# 74LVC2G157_breakout.net
KiCad netlist of a schematic drawn in EAGLE
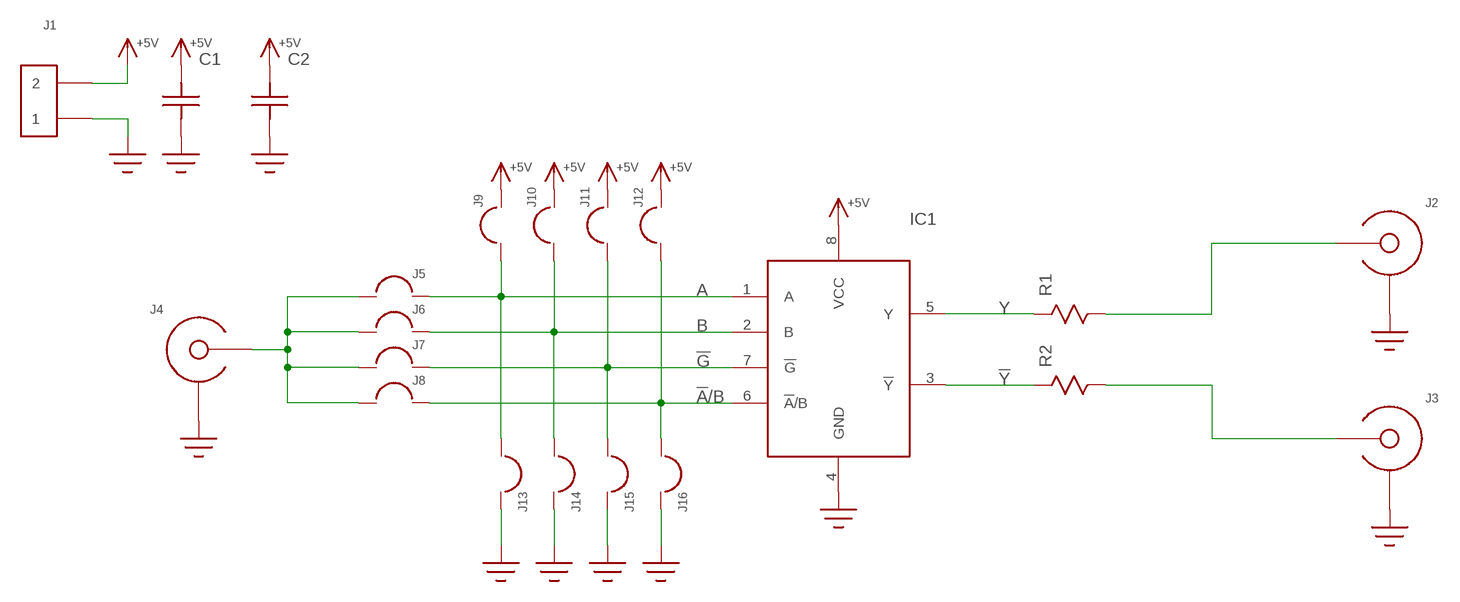
[diagram p0: schematic, sheet 1]

(export (version "E")
  (design (tool "Eeschema 10.0.6"))
  (components
    (comp (ref "C1")
      (value "C0603")
      (footprint "eagle-import:C0603")
      (libsource (lib "eagle-import") (part "C0603"))
    )
    (comp (ref "C2")
      (value "C1206")
      (footprint "eagle-import:1206")
      (libsource (lib "eagle-import") (part "C1206"))
    )
    (comp (ref "IC1")
      (value "74LVC2G157")
      (footprint "eagle-import:SSOP8")
      (libsource (lib "eagle-import") (part "74LVC2G157"))
    )
    (comp (ref "J1")
      (value "HEADER_2PIN")
      (footprint "eagle-import:HEADER_2PIN")
      (libsource (lib "eagle-import") (part "HEADER_2PIN"))
    )
    (comp (ref "J2")
      (value "EDGE_LAUNCH_JACKNARROW")
      (footprint "eagle-import:EDGE_LAUNCH_RF_CON_NARROW")
      (libsource (lib "eagle-import") (part "EDGE_LAUNCH_JACKNARROW"))
    )
    (comp (ref "J3")
      (value "EDGE_LAUNCH_JACKNARROW")
      (footprint "eagle-import:EDGE_LAUNCH_RF_CON_NARROW")
      (libsource (lib "eagle-import") (part "EDGE_LAUNCH_JACKNARROW"))
    )
    (comp (ref "J4")
      (value "EDGE_LAUNCH_JACKNARROW")
      (footprint "eagle-import:EDGE_LAUNCH_RF_CON_NARROW")
      (libsource (lib "eagle-import") (part "EDGE_LAUNCH_JACKNARROW"))
    )
    (comp (ref "J5")
      (value "SOLDER_BRIDGE")
      (footprint "eagle-import:SOLDER_BRIDGE")
      (libsource (lib "eagle-import") (part "SOLDER_BRIDGE"))
    )
    (comp (ref "J6")
      (value "SOLDER_BRIDGE")
      (footprint "eagle-import:SOLDER_BRIDGE")
      (libsource (lib "eagle-import") (part "SOLDER_BRIDGE"))
    )
    (comp (ref "J7")
      (value "SOLDER_BRIDGE")
      (footprint "eagle-import:SOLDER_BRIDGE")
      (libsource (lib "eagle-import") (part "SOLDER_BRIDGE"))
    )
    (comp (ref "J8")
      (value "SOLDER_BRIDGE")
      (footprint "eagle-import:SOLDER_BRIDGE")
      (libsource (lib "eagle-import") (part "SOLDER_BRIDGE"))
    )
    (comp (ref "J9")
      (value "SOLDER_BRIDGE")
      (footprint "eagle-import:SOLDER_BRIDGE")
      (libsource (lib "eagle-import") (part "SOLDER_BRIDGE"))
    )
    (comp (ref "J10")
      (value "SOLDER_BRIDGE")
      (footprint "eagle-import:SOLDER_BRIDGE")
      (libsource (lib "eagle-import") (part "SOLDER_BRIDGE"))
    )
    (comp (ref "J11")
      (value "SOLDER_BRIDGE")
      (footprint "eagle-import:SOLDER_BRIDGE")
      (libsource (lib "eagle-import") (part "SOLDER_BRIDGE"))
    )
    (comp (ref "J12")
      (value "SOLDER_BRIDGE")
      (footprint "eagle-import:SOLDER_BRIDGE")
      (libsource (lib "eagle-import") (part "SOLDER_BRIDGE"))
    )
    (comp (ref "J13")
      (value "SOLDER_BRIDGE")
      (footprint "eagle-import:SOLDER_BRIDGE")
      (libsource (lib "eagle-import") (part "SOLDER_BRIDGE"))
    )
    (comp (ref "J14")
      (value "SOLDER_BRIDGE")
      (footprint "eagle-import:SOLDER_BRIDGE")
      (libsource (lib "eagle-import") (part "SOLDER_BRIDGE"))
    )
    (comp (ref "J15")
      (value "SOLDER_BRIDGE")
      (footprint "eagle-import:SOLDER_BRIDGE")
      (libsource (lib "eagle-import") (part "SOLDER_BRIDGE"))
    )
    (comp (ref "J16")
      (value "SOLDER_BRIDGE")
      (footprint "eagle-import:SOLDER_BRIDGE")
      (libsource (lib "eagle-import") (part "SOLDER_BRIDGE"))
    )
    (comp (ref "R1")
      (value "R0603")
      (footprint "eagle-import:R0603")
      (libsource (lib "eagle-import") (part "R0603"))
    )
    (comp (ref "R2")
      (value "R0603")
      (footprint "eagle-import:R0603")
      (libsource (lib "eagle-import") (part "R0603"))
    )
  )
  (nets
    (net (code "1") (name "+5V") (class "Default")
      (node (ref "C1") (pin "P$2") (pinfunction "P$2_P$2") (pintype "bidirectional"))
      (node (ref "C2") (pin "P$2") (pinfunction "P$2_P$2") (pintype "bidirectional"))
      (node (ref "IC1") (pin "8") (pinfunction "VCC_8") (pintype "bidirectional"))
      (node (ref "J1") (pin "2") (pinfunction "2_2") (pintype "bidirectional"))
      (node (ref "J10") (pin "2@1") (pinfunction "P$2_2@1") (pintype "bidirectional"))
      (node (ref "J10") (pin "2@2") (pinfunction "P$2_2@2") (pintype "bidirectional"))
      (node (ref "J10") (pin "2@3") (pinfunction "P$2_2@3") (pintype "bidirectional"))
      (node (ref "J11") (pin "2@1") (pinfunction "P$2_2@1") (pintype "bidirectional"))
      (node (ref "J11") (pin "2@2") (pinfunction "P$2_2@2") (pintype "bidirectional"))
      (node (ref "J11") (pin "2@3") (pinfunction "P$2_2@3") (pintype "bidirectional"))
      (node (ref "J12") (pin "2@1") (pinfunction "P$2_2@1") (pintype "bidirectional"))
      (node (ref "J12") (pin "2@2") (pinfunction "P$2_2@2") (pintype "bidirectional"))
      (node (ref "J12") (pin "2@3") (pinfunction "P$2_2@3") (pintype "bidirectional"))
      (node (ref "J9") (pin "2@1") (pinfunction "P$2_2@1") (pintype "bidirectional"))
      (node (ref "J9") (pin "2@2") (pinfunction "P$2_2@2") (pintype "bidirectional"))
      (node (ref "J9") (pin "2@3") (pinfunction "P$2_2@3") (pintype "bidirectional"))
    )
    (net (code "2") (name "/A") (class "Default")
      (node (ref "IC1") (pin "1") (pinfunction "A_1") (pintype "bidirectional"))
      (node (ref "J13") (pin "1") (pinfunction "P$1_1") (pintype "bidirectional"))
      (node (ref "J5") (pin "2@1") (pinfunction "P$2_2@1") (pintype "bidirectional"))
      (node (ref "J5") (pin "2@2") (pinfunction "P$2_2@2") (pintype "bidirectional"))
      (node (ref "J5") (pin "2@3") (pinfunction "P$2_2@3") (pintype "bidirectional"))
      (node (ref "J9") (pin "1") (pinfunction "P$1_1") (pintype "bidirectional"))
    )
    (net (code "3") (name "/B") (class "Default")
      (node (ref "IC1") (pin "2") (pinfunction "B_2") (pintype "bidirectional"))
      (node (ref "J10") (pin "1") (pinfunction "P$1_1") (pintype "bidirectional"))
      (node (ref "J14") (pin "1") (pinfunction "P$1_1") (pintype "bidirectional"))
      (node (ref "J6") (pin "2@1") (pinfunction "P$2_2@1") (pintype "bidirectional"))
      (node (ref "J6") (pin "2@2") (pinfunction "P$2_2@2") (pintype "bidirectional"))
      (node (ref "J6") (pin "2@3") (pinfunction "P$2_2@3") (pintype "bidirectional"))
    )
    (net (code "4") (name "/Y") (class "Default")
      (node (ref "IC1") (pin "5") (pinfunction "Y_5") (pintype "bidirectional"))
      (node (ref "R1") (pin "P$1") (pinfunction "P$3_P$1") (pintype "bidirectional"))
    )
    (net (code "5") (name "/~{A}{slash}B") (class "Default")
      (node (ref "IC1") (pin "6") (pinfunction "~{A}/B_6") (pintype "bidirectional"))
      (node (ref "J12") (pin "1") (pinfunction "P$1_1") (pintype "bidirectional"))
      (node (ref "J16") (pin "1") (pinfunction "P$1_1") (pintype "bidirectional"))
      (node (ref "J8") (pin "2@1") (pinfunction "P$2_2@1") (pintype "bidirectional"))
      (node (ref "J8") (pin "2@2") (pinfunction "P$2_2@2") (pintype "bidirectional"))
      (node (ref "J8") (pin "2@3") (pinfunction "P$2_2@3") (pintype "bidirectional"))
    )
    (net (code "6") (name "/~{G}") (class "Default")
      (node (ref "IC1") (pin "7") (pinfunction "~{G}_7") (pintype "bidirectional"))
      (node (ref "J11") (pin "1") (pinfunction "P$1_1") (pintype "bidirectional"))
      (node (ref "J15") (pin "1") (pinfunction "P$1_1") (pintype "bidirectional"))
      (node (ref "J7") (pin "2@1") (pinfunction "P$2_2@1") (pintype "bidirectional"))
      (node (ref "J7") (pin "2@2") (pinfunction "P$2_2@2") (pintype "bidirectional"))
      (node (ref "J7") (pin "2@3") (pinfunction "P$2_2@3") (pintype "bidirectional"))
    )
    (net (code "7") (name "/~{Y}") (class "Default")
      (node (ref "IC1") (pin "3") (pinfunction "~{Y}_3") (pintype "bidirectional"))
      (node (ref "R2") (pin "P$1") (pinfunction "P$3_P$1") (pintype "bidirectional"))
    )
    (net (code "8") (name "GND") (class "Default")
      (node (ref "C1") (pin "P$1") (pinfunction "P$1_P$1") (pintype "bidirectional"))
      (node (ref "C2") (pin "P$1") (pinfunction "P$1_P$1") (pintype "bidirectional"))
      (node (ref "IC1") (pin "4") (pinfunction "GND_4") (pintype "bidirectional"))
      (node (ref "J1") (pin "1") (pinfunction "1_1") (pintype "bidirectional"))
      (node (ref "J13") (pin "2@1") (pinfunction "P$2_2@1") (pintype "bidirectional"))
      (node (ref "J13") (pin "2@2") (pinfunction "P$2_2@2") (pintype "bidirectional"))
      (node (ref "J13") (pin "2@3") (pinfunction "P$2_2@3") (pintype "bidirectional"))
      (node (ref "J14") (pin "2@1") (pinfunction "P$2_2@1") (pintype "bidirectional"))
      (node (ref "J14") (pin "2@2") (pinfunction "P$2_2@2") (pintype "bidirectional"))
      (node (ref "J14") (pin "2@3") (pinfunction "P$2_2@3") (pintype "bidirectional"))
      (node (ref "J15") (pin "2@1") (pinfunction "P$2_2@1") (pintype "bidirectional"))
      (node (ref "J15") (pin "2@2") (pinfunction "P$2_2@2") (pintype "bidirectional"))
      (node (ref "J15") (pin "2@3") (pinfunction "P$2_2@3") (pintype "bidirectional"))
      (node (ref "J16") (pin "2@1") (pinfunction "P$2_2@1") (pintype "bidirectional"))
      (node (ref "J16") (pin "2@2") (pinfunction "P$2_2@2") (pintype "bidirectional"))
      (node (ref "J16") (pin "2@3") (pinfunction "P$2_2@3") (pintype "bidirectional"))
      (node (ref "J2") (pin "GND@1") (pinfunction "SHIELD_GND@1") (pintype "bidirectional"))
      (node (ref "J2") (pin "GND@2") (pinfunction "SHIELD_GND@2") (pintype "bidirectional"))
      (node (ref "J2") (pin "GND@3") (pinfunction "SHIELD_GND@3") (pintype "bidirectional"))
      (node (ref "J2") (pin "GND@4") (pinfunction "SHIELD_GND@4") (pintype "bidirectional"))
      (node (ref "J2") (pin "GND@5") (pinfunction "SHIELD_GND@5") (pintype "bidirectional"))
      (node (ref "J2") (pin "GND@6") (pinfunction "SHIELD_GND@6") (pintype "bidirectional"))
      (node (ref "J2") (pin "SHIELD@1") (pinfunction "SHIELD_SHIELD@1") (pintype "bidirectional"))
      (node (ref "J2") (pin "SHIELD@2") (pinfunction "SHIELD_SHIELD@2") (pintype "bidirectional"))
      (node (ref "J3") (pin "GND@1") (pinfunction "SHIELD_GND@1") (pintype "bidirectional"))
      (node (ref "J3") (pin "GND@2") (pinfunction "SHIELD_GND@2") (pintype "bidirectional"))
      (node (ref "J3") (pin "GND@3") (pinfunction "SHIELD_GND@3") (pintype "bidirectional"))
      (node (ref "J3") (pin "GND@4") (pinfunction "SHIELD_GND@4") (pintype "bidirectional"))
      (node (ref "J3") (pin "GND@5") (pinfunction "SHIELD_GND@5") (pintype "bidirectional"))
      (node (ref "J3") (pin "GND@6") (pinfunction "SHIELD_GND@6") (pintype "bidirectional"))
      (node (ref "J3") (pin "SHIELD@1") (pinfunction "SHIELD_SHIELD@1") (pintype "bidirectional"))
      (node (ref "J3") (pin "SHIELD@2") (pinfunction "SHIELD_SHIELD@2") (pintype "bidirectional"))
      (node (ref "J4") (pin "GND@1") (pinfunction "SHIELD_GND@1") (pintype "bidirectional"))
      (node (ref "J4") (pin "GND@2") (pinfunction "SHIELD_GND@2") (pintype "bidirectional"))
      (node (ref "J4") (pin "GND@3") (pinfunction "SHIELD_GND@3") (pintype "bidirectional"))
      (node (ref "J4") (pin "GND@4") (pinfunction "SHIELD_GND@4") (pintype "bidirectional"))
      (node (ref "J4") (pin "GND@5") (pinfunction "SHIELD_GND@5") (pintype "bidirectional"))
      (node (ref "J4") (pin "GND@6") (pinfunction "SHIELD_GND@6") (pintype "bidirectional"))
      (node (ref "J4") (pin "SHIELD@1") (pinfunction "SHIELD_SHIELD@1") (pintype "bidirectional"))
      (node (ref "J4") (pin "SHIELD@2") (pinfunction "SHIELD_SHIELD@2") (pintype "bidirectional"))
    )
    (net (code "9") (name "Net-(J5-P$1)") (class "Default")
      (node (ref "J4") (pin "CENTER") (pinfunction "CENTER_CENTER") (pintype "bidirectional"))
      (node (ref "J5") (pin "1") (pinfunction "P$1_1") (pintype "bidirectional"))
      (node (ref "J6") (pin "1") (pinfunction "P$1_1") (pintype "bidirectional"))
      (node (ref "J7") (pin "1") (pinfunction "P$1_1") (pintype "bidirectional"))
      (node (ref "J8") (pin "1") (pinfunction "P$1_1") (pintype "bidirectional"))
    )
    (net (code "10") (name "Net-(R1-P$4)") (class "Default")
      (node (ref "J2") (pin "CENTER") (pinfunction "CENTER_CENTER") (pintype "bidirectional"))
      (node (ref "R1") (pin "P$2") (pinfunction "P$4_P$2") (pintype "bidirectional"))
    )
    (net (code "11") (name "Net-(R2-P$4)") (class "Default")
      (node (ref "J3") (pin "CENTER") (pinfunction "CENTER_CENTER") (pintype "bidirectional"))
      (node (ref "R2") (pin "P$2") (pinfunction "P$4_P$2") (pintype "bidirectional"))
    )
  )
)
